# ProgrammateurFilPilote_1_3.net
KiCad netlist of a schematic drawn in EAGLE
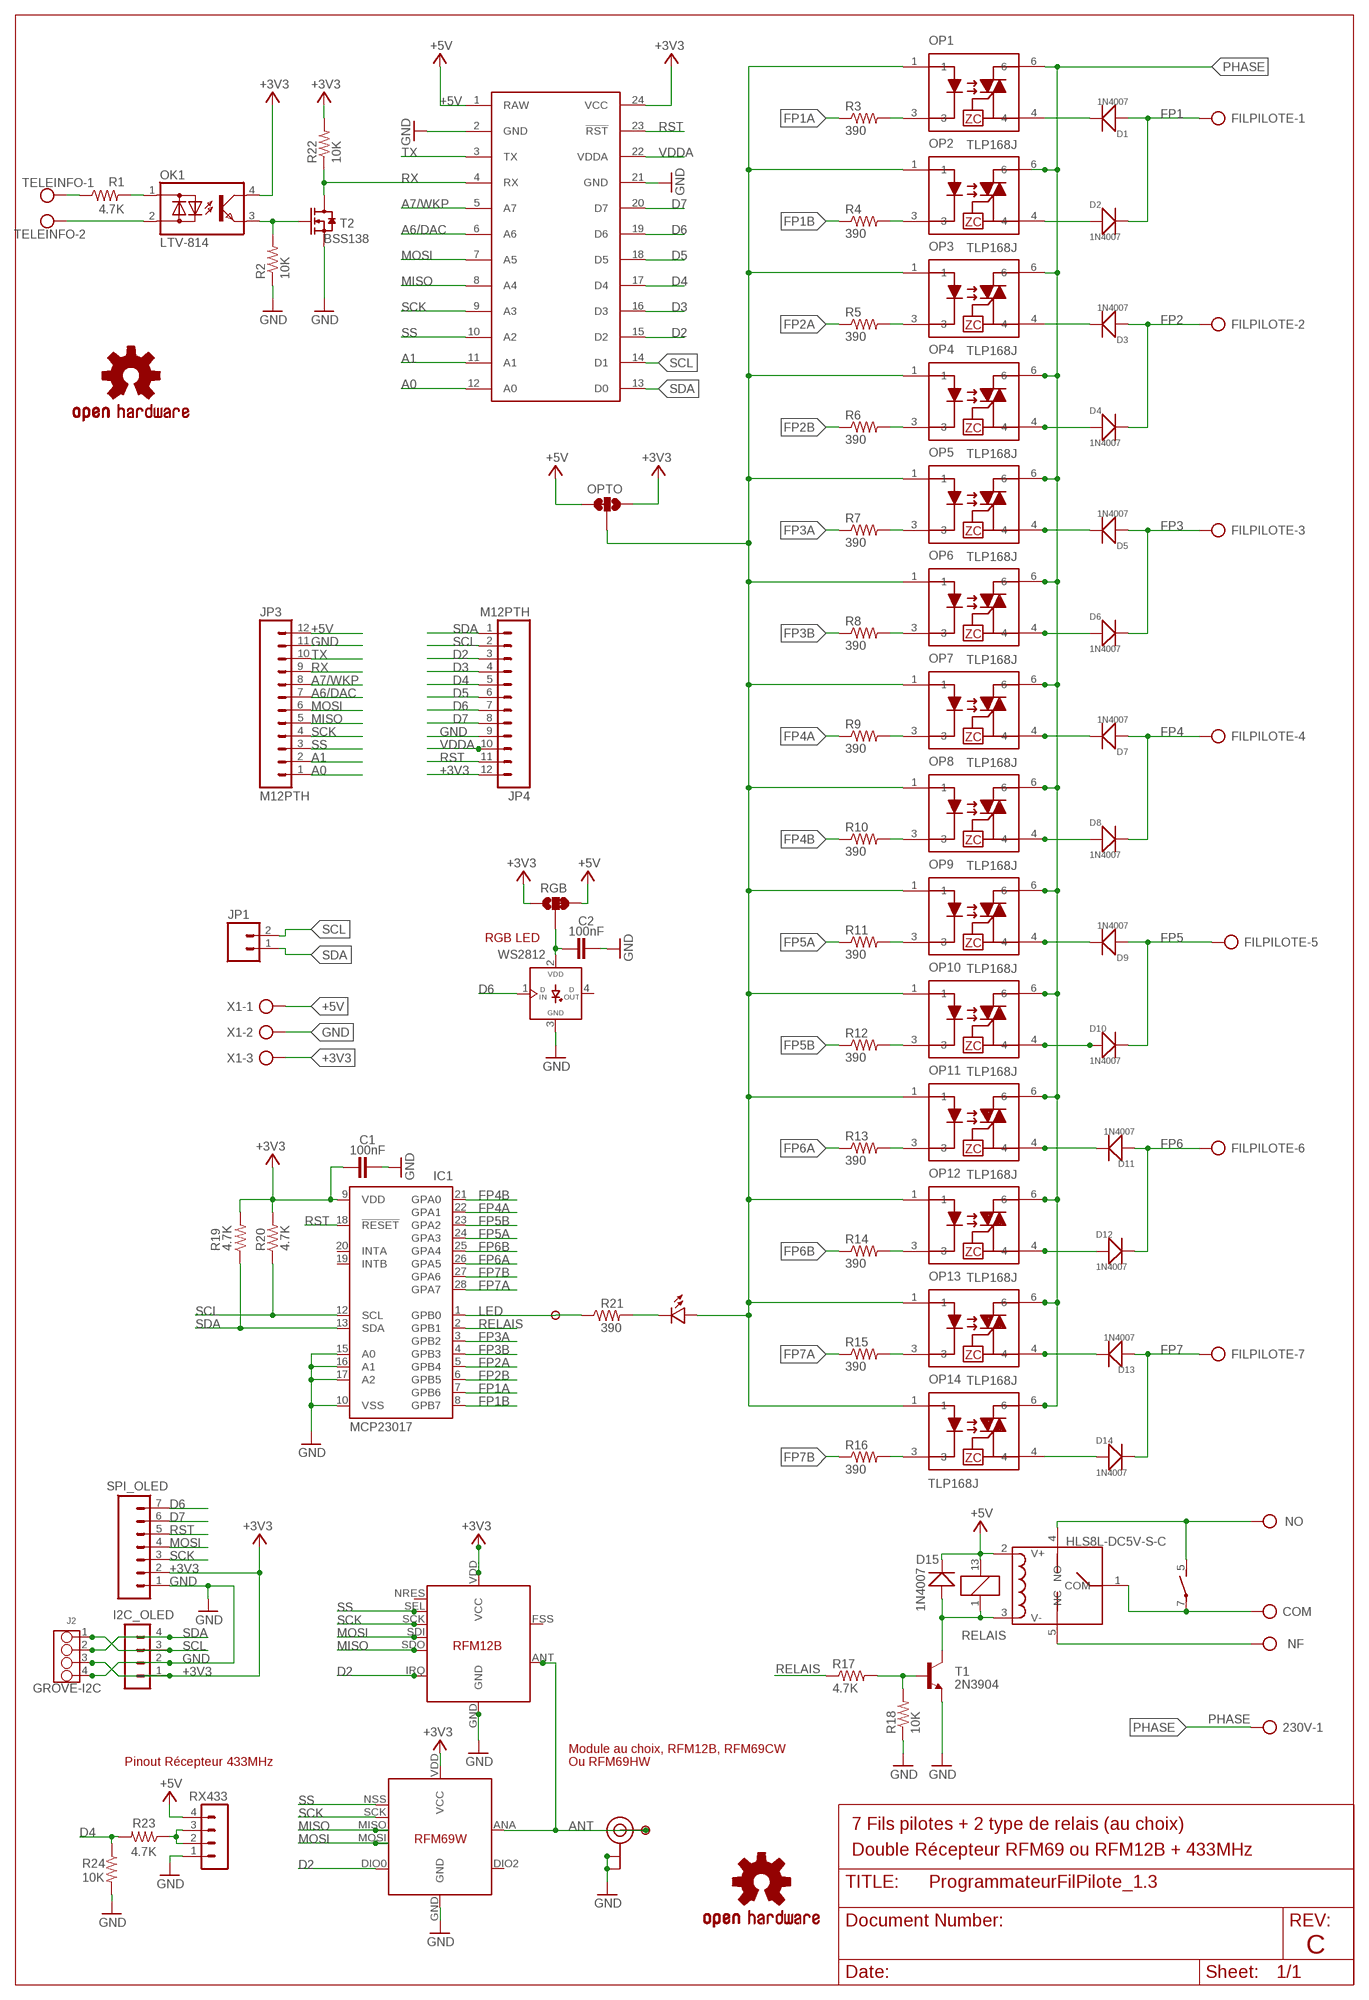
[diagram p0: schematic, sheet 1]

(export (version "E")
  (design (tool "Eeschema 10.0.6"))
  (components
    (comp (ref "230V")
      (value "AK500/2")
      (footprint "eagle-import:AK500_2")
      (libsource (lib "eagle-import") (part "AK500/2"))
    )
    (comp (ref "C1")
      (value "100nF")
      (footprint "eagle-import:1206-CAP")
      (libsource (lib "eagle-import") (part "CAP'1206-CAP'"))
    )
    (comp (ref "C2")
      (value "100nF")
      (footprint "eagle-import:1206-CAP")
      (libsource (lib "eagle-import") (part "CAP'1206-CAP'"))
    )
    (comp (ref "D1")
      (value "1N4007")
      (footprint "eagle-import:DO-214AC")
      (libsource (lib "eagle-import") (part "DIODE'SMA'"))
    )
    (comp (ref "D2")
      (value "1N4007")
      (footprint "eagle-import:DO-214AC")
      (libsource (lib "eagle-import") (part "DIODE'SMA'"))
    )
    (comp (ref "D3")
      (value "1N4007")
      (footprint "eagle-import:DO-214AC")
      (libsource (lib "eagle-import") (part "DIODE'SMA'"))
    )
    (comp (ref "D4")
      (value "1N4007")
      (footprint "eagle-import:DO-214AC")
      (libsource (lib "eagle-import") (part "DIODE'SMA'"))
    )
    (comp (ref "D5")
      (value "1N4007")
      (footprint "eagle-import:DO-214AC")
      (libsource (lib "eagle-import") (part "DIODE'SMA'"))
    )
    (comp (ref "D6")
      (value "1N4007")
      (footprint "eagle-import:DO-214AC")
      (libsource (lib "eagle-import") (part "DIODE'SMA'"))
    )
    (comp (ref "D7")
      (value "1N4007")
      (footprint "eagle-import:DO-214AC")
      (libsource (lib "eagle-import") (part "DIODE'SMA'"))
    )
    (comp (ref "D8")
      (value "1N4007")
      (footprint "eagle-import:DO-214AC")
      (libsource (lib "eagle-import") (part "DIODE'SMA'"))
    )
    (comp (ref "D9")
      (value "1N4007")
      (footprint "eagle-import:DO-214AC")
      (libsource (lib "eagle-import") (part "DIODE'SMA'"))
    )
    (comp (ref "D10")
      (value "1N4007")
      (footprint "eagle-import:DO-214AC")
      (libsource (lib "eagle-import") (part "DIODE'SMA'"))
    )
    (comp (ref "D11")
      (value "1N4007")
      (footprint "eagle-import:DO-214AC")
      (libsource (lib "eagle-import") (part "DIODE'SMA'"))
    )
    (comp (ref "D12")
      (value "1N4007")
      (footprint "eagle-import:DO-214AC")
      (libsource (lib "eagle-import") (part "DIODE'SMA'"))
    )
    (comp (ref "D13")
      (value "1N4007")
      (footprint "eagle-import:DO-214AC")
      (libsource (lib "eagle-import") (part "DIODE'SMA'"))
    )
    (comp (ref "D14")
      (value "1N4007")
      (footprint "eagle-import:DO-214AC")
      (libsource (lib "eagle-import") (part "DIODE'SMA'"))
    )
    (comp (ref "D15")
      (value "1N4007")
      (footprint "eagle-import:DO-214AC")
      (libsource (lib "eagle-import") (part "DIODE'SMA'"))
    )
    (comp (ref "FILPILOTE")
      (value "AK500/7")
      (footprint "eagle-import:AK500_7")
      (libsource (lib "eagle-import") (part "AK500/7"))
    )
    (comp (ref "I2C_OLED")
      (value "CON_HEADER_1X04'SMALL''")
      (footprint "eagle-import:M1X4")
      (libsource (lib "eagle-import") (part "CON_HEADER_1X04'SMALL''"))
    )
    (comp (ref "IC1")
      (value "MCP23017")
      (footprint "eagle-import:DIL28-3")
      (libsource (lib "eagle-import") (part "MCP23017SP"))
    )
    (comp (ref "J2")
      (value "GROVE-I2C")
      (footprint "eagle-import:4P-2.0")
      (libsource (lib "eagle-import") (part "GROVE-4P-2.0-3470130P1"))
    )
    (comp (ref "JP1")
      (value "M02PTH")
      (footprint "eagle-import:1X02")
      (libsource (lib "eagle-import") (part "M02PTH"))
    )
    (comp (ref "JP3")
      (value "M12PTH")
      (footprint "eagle-import:1X12-SMALL-PADS")
      (libsource (lib "eagle-import") (part "M12PTH"))
    )
    (comp (ref "JP4")
      (value "M12PTH")
      (footprint "eagle-import:1X12-SMALL-PADS")
      (libsource (lib "eagle-import") (part "M12PTH"))
    )
    (comp (ref "LED")
      (value "LED3MM")
      (footprint "eagle-import:LED3MM")
      (libsource (lib "eagle-import") (part "LED3MM"))
    )
    (comp (ref "LOGO1")
      (value "OSHW-LOGOL")
      (footprint "eagle-import:OSHW-LOGO-L")
      (libsource (lib "eagle-import") (part "OSHW-LOGOL"))
    )
    (comp (ref "LOGO2")
      (value "OSHW-LOGOL")
      (footprint "eagle-import:OSHW-LOGO-L")
      (libsource (lib "eagle-import") (part "OSHW-LOGOL"))
    )
    (comp (ref "OK1")
      (value "LTV-814")
      (footprint "eagle-import:DIL4-SMD")
      (fields (field (name "MF") "VISHAY/TELEFUNKEN") (field (name "MPN") "SFH6206-3"))
      (libsource (lib "eagle-import") (part "SFH6206"))
    )
    (comp (ref "OP1")
      (value "TLP168J")
      (footprint "eagle-import:MFSOP-4-HANDSOLDER")
      (libsource (lib "eagle-import") (part "TLP168JBIGPAD"))
    )
    (comp (ref "OP2")
      (value "TLP168J")
      (footprint "eagle-import:MFSOP-4-HANDSOLDER")
      (libsource (lib "eagle-import") (part "TLP168JBIGPAD"))
    )
    (comp (ref "OP3")
      (value "TLP168J")
      (footprint "eagle-import:MFSOP-4-HANDSOLDER")
      (libsource (lib "eagle-import") (part "TLP168JBIGPAD"))
    )
    (comp (ref "OP4")
      (value "TLP168J")
      (footprint "eagle-import:MFSOP-4-HANDSOLDER")
      (libsource (lib "eagle-import") (part "TLP168JBIGPAD"))
    )
    (comp (ref "OP5")
      (value "TLP168J")
      (footprint "eagle-import:MFSOP-4-HANDSOLDER")
      (libsource (lib "eagle-import") (part "TLP168JBIGPAD"))
    )
    (comp (ref "OP6")
      (value "TLP168J")
      (footprint "eagle-import:MFSOP-4-HANDSOLDER")
      (libsource (lib "eagle-import") (part "TLP168JBIGPAD"))
    )
    (comp (ref "OP7")
      (value "TLP168J")
      (footprint "eagle-import:MFSOP-4-HANDSOLDER")
      (libsource (lib "eagle-import") (part "TLP168JBIGPAD"))
    )
    (comp (ref "OP8")
      (value "TLP168J")
      (footprint "eagle-import:MFSOP-4-HANDSOLDER")
      (libsource (lib "eagle-import") (part "TLP168JBIGPAD"))
    )
    (comp (ref "OP9")
      (value "TLP168J")
      (footprint "eagle-import:MFSOP-4-HANDSOLDER")
      (libsource (lib "eagle-import") (part "TLP168JBIGPAD"))
    )
    (comp (ref "OP10")
      (value "TLP168J")
      (footprint "eagle-import:MFSOP-4-HANDSOLDER")
      (libsource (lib "eagle-import") (part "TLP168JBIGPAD"))
    )
    (comp (ref "OP11")
      (value "TLP168J")
      (footprint "eagle-import:MFSOP-4-HANDSOLDER")
      (libsource (lib "eagle-import") (part "TLP168JBIGPAD"))
    )
    (comp (ref "OP12")
      (value "TLP168J")
      (footprint "eagle-import:MFSOP-4-HANDSOLDER")
      (libsource (lib "eagle-import") (part "TLP168JBIGPAD"))
    )
    (comp (ref "OP13")
      (value "TLP168J")
      (footprint "eagle-import:MFSOP-4-HANDSOLDER")
      (libsource (lib "eagle-import") (part "TLP168JBIGPAD"))
    )
    (comp (ref "OP14")
      (value "TLP168J")
      (footprint "eagle-import:MFSOP-4-HANDSOLDER")
      (libsource (lib "eagle-import") (part "TLP168JBIGPAD"))
    )
    (comp (ref "OPTO")
      (value "JUMPER-PAD-3-2OF3_NC_BY_TRACE_LARGE")
      (footprint "eagle-import:PAD-JUMPER-3-2OF3_NC_BY_TRACE_YES_SILK_LARGE")
      (libsource (lib "eagle-import") (part "JUMPER-PAD-3-2OF3_NC_BY_TRACE_LARGE"))
    )
    (comp (ref "P1")
      (value "PADSMALL")
      (footprint "eagle-import:PAD-SMALL")
      (libsource (lib "eagle-import") (part "PADSMALL"))
    )
    (comp (ref "P2")
      (value "PADSMALL")
      (footprint "eagle-import:PAD-SMALL")
      (libsource (lib "eagle-import") (part "PADSMALL"))
    )
    (comp (ref "PARTICLE")
      (value "Spark/Photon")
      (footprint "eagle-import:SPARK_CORE")
      (libsource (lib "eagle-import") (part "SPARK_CORECORE"))
    )
    (comp (ref "R1")
      (value "4.7K")
      (footprint "eagle-import:1206-RES")
      (libsource (lib "eagle-import") (part "RESISTOR'1206-RES''"))
    )
    (comp (ref "R2")
      (value "10K")
      (footprint "eagle-import:1206-RES")
      (libsource (lib "eagle-import") (part "RESISTOR'1206-RES''"))
    )
    (comp (ref "R3")
      (value "390")
      (footprint "eagle-import:1206-RES")
      (libsource (lib "eagle-import") (part "RESISTOR'1206-RES''"))
    )
    (comp (ref "R4")
      (value "390")
      (footprint "eagle-import:1206-RES")
      (libsource (lib "eagle-import") (part "RESISTOR'1206-RES''"))
    )
    (comp (ref "R5")
      (value "390")
      (footprint "eagle-import:1206-RES")
      (libsource (lib "eagle-import") (part "RESISTOR'1206-RES''"))
    )
    (comp (ref "R6")
      (value "390")
      (footprint "eagle-import:1206-RES")
      (libsource (lib "eagle-import") (part "RESISTOR'1206-RES''"))
    )
    (comp (ref "R7")
      (value "390")
      (footprint "eagle-import:1206-RES")
      (libsource (lib "eagle-import") (part "RESISTOR'1206-RES''"))
    )
    (comp (ref "R8")
      (value "390")
      (footprint "eagle-import:1206-RES")
      (libsource (lib "eagle-import") (part "RESISTOR'1206-RES''"))
    )
    (comp (ref "R9")
      (value "390")
      (footprint "eagle-import:1206-RES")
      (libsource (lib "eagle-import") (part "RESISTOR'1206-RES''"))
    )
    (comp (ref "R10")
      (value "390")
      (footprint "eagle-import:1206-RES")
      (libsource (lib "eagle-import") (part "RESISTOR'1206-RES''"))
    )
    (comp (ref "R11")
      (value "390")
      (footprint "eagle-import:1206-RES")
      (libsource (lib "eagle-import") (part "RESISTOR'1206-RES''"))
    )
    (comp (ref "R12")
      (value "390")
      (footprint "eagle-import:1206-RES")
      (libsource (lib "eagle-import") (part "RESISTOR'1206-RES''"))
    )
    (comp (ref "R13")
      (value "390")
      (footprint "eagle-import:1206-RES")
      (libsource (lib "eagle-import") (part "RESISTOR'1206-RES''"))
    )
    (comp (ref "R14")
      (value "390")
      (footprint "eagle-import:1206-RES")
      (libsource (lib "eagle-import") (part "RESISTOR'1206-RES''"))
    )
    (comp (ref "R15")
      (value "390")
      (footprint "eagle-import:1206-RES")
      (libsource (lib "eagle-import") (part "RESISTOR'1206-RES''"))
    )
    (comp (ref "R16")
      (value "390")
      (footprint "eagle-import:1206-RES")
      (libsource (lib "eagle-import") (part "RESISTOR'1206-RES''"))
    )
    (comp (ref "R17")
      (value "4.7K")
      (footprint "eagle-import:1206-RES")
      (libsource (lib "eagle-import") (part "RESISTOR'1206-RES''"))
    )
    (comp (ref "R18")
      (value "10K")
      (footprint "eagle-import:1206-RES")
      (libsource (lib "eagle-import") (part "RESISTOR'1206-RES''"))
    )
    (comp (ref "R19")
      (value "4.7K")
      (footprint "eagle-import:1206-RES")
      (libsource (lib "eagle-import") (part "RESISTOR'1206-RES''"))
    )
    (comp (ref "R20")
      (value "4.7K")
      (footprint "eagle-import:1206-RES")
      (libsource (lib "eagle-import") (part "RESISTOR'1206-RES''"))
    )
    (comp (ref "R21")
      (value "390")
      (footprint "eagle-import:1206-RES")
      (libsource (lib "eagle-import") (part "RESISTOR'1206-RES''"))
    )
    (comp (ref "R22")
      (value "10K")
      (footprint "eagle-import:1206-RES")
      (libsource (lib "eagle-import") (part "RESISTOR'1206-RES''"))
    )
    (comp (ref "R23")
      (value "4.7K")
      (footprint "eagle-import:1206-RES")
      (libsource (lib "eagle-import") (part "RESISTOR'1206-RES''"))
    )
    (comp (ref "R24")
      (value "10K")
      (footprint "eagle-import:1206-RES")
      (libsource (lib "eagle-import") (part "RESISTOR'1206-RES''"))
    )
    (comp (ref "RELAIS")
      (value "Relais G6D")
      (footprint "eagle-import:G6D")
      (libsource (lib "eagle-import") (part "G6D?-1A-ASI12VDC"))
    )
    (comp (ref "RGB")
      (value "JUMPER-PAD-3-2OF3_NC_BY_TRACE_SMALL")
      (footprint "eagle-import:PAD-JUMPER-3-2OF3_NC_BY_TRACE_YES_SILK_FULL_BOX")
      (libsource (lib "eagle-import") (part "JUMPER-PAD-3-2OF3_NC_BY_TRACE_SMALL"))
    )
    (comp (ref "RL")
      (value "AK500/2")
      (footprint "eagle-import:AK500_2")
      (libsource (lib "eagle-import") (part "AK500/2"))
    )
    (comp (ref "RX433")
      (value "CON_HEADER_1X04'NO_LOCK'")
      (footprint "eagle-import:1X04_NO_LOCK")
      (libsource (lib "eagle-import") (part "CON_HEADER_1X04'NO_LOCK'"))
    )
    (comp (ref "SPI_OLED")
      (value "CON_HEADER_1X07'SMALL'")
      (footprint "eagle-import:M1X7")
      (libsource (lib "eagle-import") (part "CON_HEADER_1X07'SMALL'"))
    )
    (comp (ref "SW1")
      (value "HLS8L-DC5V-S-C")
      (footprint "eagle-import:5P-L19.0XW15.0XH15.0MM")
      (libsource (lib "eagle-import") (part "RELAY-HLS8L-DC5V-S-C-315030000"))
    )
    (comp (ref "T1")
      (value "2N3904")
      (footprint "eagle-import:TO92-EBC")
      (libsource (lib "eagle-import") (part "-NPN-TO92-EBC2N2222"))
    )
    (comp (ref "T2")
      (value "BSS138")
      (footprint "eagle-import:SOT23")
      (libsource (lib "eagle-import") (part "MOSFET-N-''"))
    )
    (comp (ref "TELEINFO")
      (value "AK500/2")
      (footprint "eagle-import:AK500_2")
      (libsource (lib "eagle-import") (part "AK500/2"))
    )
    (comp (ref "U$2")
      (value "RFM12B")
      (footprint "eagle-import:RFM12B-MINPADS")
      (libsource (lib "eagle-import") (part "RFM12B"))
    )
    (comp (ref "U$3")
      (value "RFM69W")
      (footprint "eagle-import:RFM69W-MINPADS")
      (libsource (lib "eagle-import") (part "RFM69W"))
    )
    (comp (ref "U-FL")
      (value "U.FL")
      (footprint "eagle-import:U.FL")
      (libsource (lib "eagle-import") (part "U.FL"))
    )
    (comp (ref "WS2812")
      (value "RGB LED")
      (footprint "eagle-import:WS2812-PTH")
      (libsource (lib "eagle-import") (part "WS2812B5MM"))
    )
    (comp (ref "X1")
      (value "AK500/3")
      (footprint "eagle-import:AK500_3")
      (libsource (lib "eagle-import") (part "AK500/3"))
    )
  )
  (nets
    (net (code "1") (name "+3V3") (class "Default")
      (node (ref "C1") (pin "1") (pinfunction "1_1") (pintype "passive"))
      (node (ref "I2C_OLED") (pin "1") (pinfunction "1_1") (pintype "passive"))
      (node (ref "IC1") (pin "9") (pinfunction "VDD_9") (pintype "power_in"))
      (node (ref "J2") (pin "3") (pinfunction "3_3") (pintype "bidirectional"))
      (node (ref "JP4") (pin "12") (pinfunction "12_12") (pintype "passive"))
      (node (ref "OK1") (pin "4") (pinfunction "C_4") (pintype "passive"))
      (node (ref "OPTO") (pin "1") (pinfunction "1_1") (pintype "passive"))
      (node (ref "PARTICLE") (pin "24") (pinfunction "VCC_24") (pintype "power_in"))
      (node (ref "R19") (pin "2") (pinfunction "2_2") (pintype "passive"))
      (node (ref "R20") (pin "2") (pinfunction "2_2") (pintype "passive"))
      (node (ref "R22") (pin "2") (pinfunction "2_2") (pintype "passive"))
      (node (ref "RGB") (pin "1") (pinfunction "1_1") (pintype "passive"))
      (node (ref "SPI_OLED") (pin "2") (pinfunction "2_2") (pintype "passive"))
      (node (ref "U$2") (pin "VDD") (pinfunction "VCC_VDD") (pintype "power_in"))
      (node (ref "U$3") (pin "VDD") (pinfunction "VCC_VDD") (pintype "power_in"))
      (node (ref "X1") (pin "3") (pinfunction "KL_3") (pintype "passive"))
    )
    (net (code "2") (name "+5V") (class "Default")
      (node (ref "D15") (pin "2") (pinfunction "-_2") (pintype "passive"))
      (node (ref "JP3") (pin "12") (pinfunction "12_12") (pintype "passive"))
      (node (ref "OPTO") (pin "3") (pinfunction "3_3") (pintype "passive"))
      (node (ref "PARTICLE") (pin "1") (pinfunction "RAW_1") (pintype "power_in"))
      (node (ref "RELAIS") (pin "13") (pinfunction "2_13") (pintype "passive"))
      (node (ref "RGB") (pin "3") (pinfunction "3_3") (pintype "passive"))
      (node (ref "RX433") (pin "4") (pinfunction "4_4") (pintype "passive"))
      (node (ref "SW1") (pin "2") (pinfunction "V+_2") (pintype "bidirectional"))
      (node (ref "X1") (pin "1") (pinfunction "KL_1") (pintype "passive"))
    )
    (net (code "3") (name "/A0") (class "Default")
      (node (ref "JP3") (pin "1") (pinfunction "1_1") (pintype "passive"))
      (node (ref "PARTICLE") (pin "12") (pinfunction "A0_12") (pintype "bidirectional"))
    )
    (net (code "4") (name "/A1") (class "Default")
      (node (ref "JP3") (pin "2") (pinfunction "2_2") (pintype "passive"))
      (node (ref "PARTICLE") (pin "11") (pinfunction "A1_11") (pintype "bidirectional"))
    )
    (net (code "5") (name "/A6{slash}DAC") (class "Default")
      (node (ref "JP3") (pin "7") (pinfunction "7_7") (pintype "passive"))
      (node (ref "PARTICLE") (pin "6") (pinfunction "A6_6") (pintype "bidirectional"))
    )
    (net (code "6") (name "/A7{slash}WKP") (class "Default")
      (node (ref "JP3") (pin "8") (pinfunction "8_8") (pintype "passive"))
      (node (ref "PARTICLE") (pin "5") (pinfunction "A7_5") (pintype "bidirectional"))
    )
    (net (code "7") (name "/ANT") (class "Default")
      (node (ref "P1") (pin "1") (pinfunction "1_1") (pintype "bidirectional"))
      (node (ref "U$2") (pin "ANT") (pinfunction "ANT_ANT") (pintype "passive"))
      (node (ref "U$3") (pin "ANA") (pinfunction "ANT_ANA") (pintype "passive"))
      (node (ref "U-FL") (pin "3") (pinfunction "SIGNAL_3") (pintype "passive"))
    )
    (net (code "8") (name "/COM") (class "Default")
      (node (ref "RELAIS") (pin "7") (pinfunction "P_7") (pintype "passive"))
      (node (ref "RL") (pin "1") (pinfunction "KL_1") (pintype "passive"))
      (node (ref "SW1") (pin "1") (pinfunction "COM_1") (pintype "bidirectional"))
    )
    (net (code "9") (name "/D2") (class "Default")
      (node (ref "JP4") (pin "3") (pinfunction "3_3") (pintype "passive"))
      (node (ref "PARTICLE") (pin "15") (pinfunction "D2_15") (pintype "bidirectional"))
      (node (ref "U$2") (pin "IRQ") (pinfunction "IRQ_IRQ") (pintype "open_collector"))
      (node (ref "U$3") (pin "DIO0") (pinfunction "DIO0_DIO0") (pintype "open_collector"))
    )
    (net (code "10") (name "/D3") (class "Default")
      (node (ref "JP4") (pin "4") (pinfunction "4_4") (pintype "passive"))
      (node (ref "PARTICLE") (pin "16") (pinfunction "D3_16") (pintype "bidirectional"))
    )
    (net (code "11") (name "/D4") (class "Default")
      (node (ref "JP4") (pin "5") (pinfunction "5_5") (pintype "passive"))
      (node (ref "PARTICLE") (pin "17") (pinfunction "D4_17") (pintype "bidirectional"))
      (node (ref "R23") (pin "2") (pinfunction "2_2") (pintype "passive"))
      (node (ref "R24") (pin "1") (pinfunction "1_1") (pintype "passive"))
    )
    (net (code "12") (name "/D5") (class "Default")
      (node (ref "JP4") (pin "6") (pinfunction "6_6") (pintype "passive"))
      (node (ref "PARTICLE") (pin "18") (pinfunction "D5_18") (pintype "bidirectional"))
    )
    (net (code "13") (name "/D6") (class "Default")
      (node (ref "JP4") (pin "7") (pinfunction "7_7") (pintype "passive"))
      (node (ref "PARTICLE") (pin "19") (pinfunction "D6_19") (pintype "bidirectional"))
      (node (ref "SPI_OLED") (pin "7") (pinfunction "7_7") (pintype "passive"))
      (node (ref "WS2812") (pin "1") (pinfunction "DIN_1") (pintype "input"))
    )
    (net (code "14") (name "/D7") (class "Default")
      (node (ref "JP4") (pin "8") (pinfunction "8_8") (pintype "passive"))
      (node (ref "PARTICLE") (pin "20") (pinfunction "D7_20") (pintype "bidirectional"))
      (node (ref "SPI_OLED") (pin "6") (pinfunction "6_6") (pintype "passive"))
    )
    (net (code "15") (name "/FP1") (class "Default")
      (node (ref "D1") (pin "1") (pinfunction "+_1") (pintype "passive"))
      (node (ref "D2") (pin "2") (pinfunction "-_2") (pintype "passive"))
      (node (ref "FILPILOTE") (pin "1") (pinfunction "KL_1") (pintype "passive"))
    )
    (net (code "16") (name "/FP2") (class "Default")
      (node (ref "D3") (pin "1") (pinfunction "+_1") (pintype "passive"))
      (node (ref "D4") (pin "2") (pinfunction "-_2") (pintype "passive"))
      (node (ref "FILPILOTE") (pin "2") (pinfunction "KL_2") (pintype "passive"))
    )
    (net (code "17") (name "/FP3") (class "Default")
      (node (ref "D5") (pin "1") (pinfunction "+_1") (pintype "passive"))
      (node (ref "D6") (pin "2") (pinfunction "-_2") (pintype "passive"))
      (node (ref "FILPILOTE") (pin "3") (pinfunction "KL_3") (pintype "passive"))
    )
    (net (code "18") (name "/FP4") (class "Default")
      (node (ref "D7") (pin "1") (pinfunction "+_1") (pintype "passive"))
      (node (ref "D8") (pin "2") (pinfunction "-_2") (pintype "passive"))
      (node (ref "FILPILOTE") (pin "4") (pinfunction "KL_4") (pintype "passive"))
    )
    (net (code "19") (name "/FP5") (class "Default")
      (node (ref "D10") (pin "2") (pinfunction "-_2") (pintype "passive"))
      (node (ref "D9") (pin "1") (pinfunction "+_1") (pintype "passive"))
      (node (ref "FILPILOTE") (pin "5") (pinfunction "KL_5") (pintype "passive"))
    )
    (net (code "20") (name "/FP6") (class "Default")
      (node (ref "D11") (pin "1") (pinfunction "+_1") (pintype "passive"))
      (node (ref "D12") (pin "2") (pinfunction "-_2") (pintype "passive"))
      (node (ref "FILPILOTE") (pin "6") (pinfunction "KL_6") (pintype "passive"))
    )
    (net (code "21") (name "/FP7") (class "Default")
      (node (ref "D13") (pin "1") (pinfunction "+_1") (pintype "passive"))
      (node (ref "D14") (pin "2") (pinfunction "-_2") (pintype "passive"))
      (node (ref "FILPILOTE") (pin "7") (pinfunction "KL_7") (pintype "passive"))
    )
    (net (code "22") (name "/LED") (class "Default")
      (node (ref "IC1") (pin "1") (pinfunction "GPB0_1") (pintype "bidirectional"))
      (node (ref "P2") (pin "1") (pinfunction "1_1") (pintype "bidirectional"))
      (node (ref "R21") (pin "1") (pinfunction "1_1") (pintype "passive"))
    )
    (net (code "23") (name "/MISO") (class "Default")
      (node (ref "JP3") (pin "5") (pinfunction "5_5") (pintype "passive"))
      (node (ref "PARTICLE") (pin "8") (pinfunction "A4_8") (pintype "bidirectional"))
      (node (ref "U$2") (pin "SDO") (pinfunction "SDO_SDO") (pintype "output"))
      (node (ref "U$3") (pin "MISO") (pinfunction "MISO_MISO") (pintype "input"))
    )
    (net (code "24") (name "/MOSI") (class "Default")
      (node (ref "JP3") (pin "6") (pinfunction "6_6") (pintype "passive"))
      (node (ref "PARTICLE") (pin "7") (pinfunction "A5_7") (pintype "bidirectional"))
      (node (ref "SPI_OLED") (pin "4") (pinfunction "4_4") (pintype "passive"))
      (node (ref "U$2") (pin "SDI") (pinfunction "SDI_SDI") (pintype "input"))
      (node (ref "U$3") (pin "MOSI") (pinfunction "MOSI_MOSI") (pintype "output"))
    )
    (net (code "25") (name "/NF") (class "Default")
      (node (ref "RL") (pin "2") (pinfunction "KL_2") (pintype "passive"))
      (node (ref "SW1") (pin "5") (pinfunction "NC_5") (pintype "bidirectional"))
    )
    (net (code "26") (name "/NO") (class "Default")
      (node (ref "230V") (pin "2") (pinfunction "KL_2") (pintype "passive"))
      (node (ref "RELAIS") (pin "5") (pinfunction "S_5") (pintype "passive"))
      (node (ref "SW1") (pin "4") (pinfunction "NO_4") (pintype "bidirectional"))
    )
    (net (code "27") (name "/RELAIS") (class "Default")
      (node (ref "IC1") (pin "2") (pinfunction "GPB1_2") (pintype "bidirectional"))
      (node (ref "R17") (pin "1") (pinfunction "1_1") (pintype "passive"))
    )
    (net (code "28") (name "/RST") (class "Default")
      (node (ref "IC1") (pin "18") (pinfunction "~{RESET}_18") (pintype "input"))
      (node (ref "JP4") (pin "11") (pinfunction "11_11") (pintype "passive"))
      (node (ref "PARTICLE") (pin "23") (pinfunction "~{RST}_23") (pintype "bidirectional"))
      (node (ref "SPI_OLED") (pin "5") (pinfunction "5_5") (pintype "passive"))
    )
    (net (code "29") (name "/RX") (class "Default")
      (node (ref "JP3") (pin "9") (pinfunction "9_9") (pintype "passive"))
      (node (ref "PARTICLE") (pin "4") (pinfunction "RX_4") (pintype "bidirectional"))
      (node (ref "R22") (pin "1") (pinfunction "1_1") (pintype "passive"))
      (node (ref "T2") (pin "3") (pinfunction "D_3") (pintype "passive"))
    )
    (net (code "30") (name "/SCK") (class "Default")
      (node (ref "JP3") (pin "4") (pinfunction "4_4") (pintype "passive"))
      (node (ref "PARTICLE") (pin "9") (pinfunction "A3_9") (pintype "bidirectional"))
      (node (ref "SPI_OLED") (pin "3") (pinfunction "3_3") (pintype "passive"))
      (node (ref "U$2") (pin "SCK") (pinfunction "SCK_SCK") (pintype "input"))
      (node (ref "U$3") (pin "SCK") (pinfunction "SCK_SCK") (pintype "input"))
    )
    (net (code "31") (name "/SS") (class "Default")
      (node (ref "JP3") (pin "3") (pinfunction "3_3") (pintype "passive"))
      (node (ref "PARTICLE") (pin "10") (pinfunction "A2_10") (pintype "bidirectional"))
      (node (ref "U$2") (pin "SEL") (pinfunction "SEL_SEL") (pintype "input"))
      (node (ref "U$3") (pin "NSS") (pinfunction "SEL_NSS") (pintype "input"))
    )
    (net (code "32") (name "/TX") (class "Default")
      (node (ref "JP3") (pin "10") (pinfunction "10_10") (pintype "passive"))
      (node (ref "PARTICLE") (pin "3") (pinfunction "TX_3") (pintype "bidirectional"))
    )
    (net (code "33") (name "/VDDA") (class "Default")
      (node (ref "JP4") (pin "10") (pinfunction "10_10") (pintype "passive"))
      (node (ref "PARTICLE") (pin "22") (pinfunction "VDDA_22") (pintype "power_in"))
    )
    (net (code "34") (name "FP1A") (class "Default")
      (node (ref "IC1") (pin "7") (pinfunction "GPB6_7") (pintype "bidirectional"))
      (node (ref "R3") (pin "1") (pinfunction "1_1") (pintype "passive"))
    )
    (net (code "35") (name "FP1B") (class "Default")
      (node (ref "IC1") (pin "8") (pinfunction "GPB7_8") (pintype "bidirectional"))
      (node (ref "R4") (pin "1") (pinfunction "1_1") (pintype "passive"))
    )
    (net (code "36") (name "FP2A") (class "Default")
      (node (ref "IC1") (pin "5") (pinfunction "GPB4_5") (pintype "bidirectional"))
      (node (ref "R5") (pin "1") (pinfunction "1_1") (pintype "passive"))
    )
    (net (code "37") (name "FP2B") (class "Default")
      (node (ref "IC1") (pin "6") (pinfunction "GPB5_6") (pintype "bidirectional"))
      (node (ref "R6") (pin "1") (pinfunction "1_1") (pintype "passive"))
    )
    (net (code "38") (name "FP3A") (class "Default")
      (node (ref "IC1") (pin "3") (pinfunction "GPB2_3") (pintype "bidirectional"))
      (node (ref "R7") (pin "1") (pinfunction "1_1") (pintype "passive"))
    )
    (net (code "39") (name "FP3B") (class "Default")
      (node (ref "IC1") (pin "4") (pinfunction "GPB3_4") (pintype "bidirectional"))
      (node (ref "R8") (pin "1") (pinfunction "1_1") (pintype "passive"))
    )
    (net (code "40") (name "FP4A") (class "Default")
      (node (ref "IC1") (pin "22") (pinfunction "GPA1_22") (pintype "bidirectional"))
      (node (ref "R9") (pin "1") (pinfunction "1_1") (pintype "passive"))
    )
    (net (code "41") (name "FP4B") (class "Default")
      (node (ref "IC1") (pin "21") (pinfunction "GPA0_21") (pintype "bidirectional"))
      (node (ref "R10") (pin "1") (pinfunction "1_1") (pintype "passive"))
    )
    (net (code "42") (name "FP5A") (class "Default")
      (node (ref "IC1") (pin "24") (pinfunction "GPA3_24") (pintype "bidirectional"))
      (node (ref "R11") (pin "1") (pinfunction "1_1") (pintype "passive"))
    )
    (net (code "43") (name "FP5B") (class "Default")
      (node (ref "IC1") (pin "23") (pinfunction "GPA2_23") (pintype "bidirectional"))
      (node (ref "R12") (pin "1") (pinfunction "1_1") (pintype "passive"))
    )
    (net (code "44") (name "FP6A") (class "Default")
      (node (ref "IC1") (pin "26") (pinfunction "GPA5_26") (pintype "bidirectional"))
      (node (ref "R13") (pin "1") (pinfunction "1_1") (pintype "passive"))
    )
    (net (code "45") (name "FP6B") (class "Default")
      (node (ref "IC1") (pin "25") (pinfunction "GPA4_25") (pintype "bidirectional"))
      (node (ref "R14") (pin "1") (pinfunction "1_1") (pintype "passive"))
    )
    (net (code "46") (name "FP7A") (class "Default")
      (node (ref "IC1") (pin "28") (pinfunction "GPA7_28") (pintype "bidirectional"))
      (node (ref "R15") (pin "1") (pinfunction "1_1") (pintype "passive"))
    )
    (net (code "47") (name "FP7B") (class "Default")
      (node (ref "IC1") (pin "27") (pinfunction "GPA6_27") (pintype "bidirectional"))
      (node (ref "R16") (pin "1") (pinfunction "1_1") (pintype "passive"))
    )
    (net (code "48") (name "GND") (class "Default")
      (node (ref "C1") (pin "2") (pinfunction "2_2") (pintype "passive"))
      (node (ref "C2") (pin "2") (pinfunction "2_2") (pintype "passive"))
      (node (ref "I2C_OLED") (pin "2") (pinfunction "2_2") (pintype "passive"))
      (node (ref "IC1") (pin "10") (pinfunction "VSS_10") (pintype "power_in"))
      (node (ref "IC1") (pin "15") (pinfunction "A0_15") (pintype "input"))
      (node (ref "IC1") (pin "16") (pinfunction "A1_16") (pintype "input"))
      (node (ref "IC1") (pin "17") (pinfunction "A2_17") (pintype "input"))
      (node (ref "J2") (pin "4") (pinfunction "4_4") (pintype "bidirectional"))
      (node (ref "JP3") (pin "11") (pinfunction "11_11") (pintype "passive"))
      (node (ref "JP4") (pin "9") (pinfunction "9_9") (pintype "passive"))
      (node (ref "PARTICLE") (pin "2") (pinfunction "GND_2") (pintype "power_in"))
      (node (ref "PARTICLE") (pin "21") (pinfunction "GND_21") (pintype "power_in"))
      (node (ref "R18") (pin "1") (pinfunction "1_1") (pintype "passive"))
      (node (ref "R2") (pin "1") (pinfunction "1_1") (pintype "passive"))
      (node (ref "R24") (pin "2") (pinfunction "2_2") (pintype "passive"))
      (node (ref "RX433") (pin "1") (pinfunction "1_1") (pintype "passive"))
      (node (ref "SPI_OLED") (pin "1") (pinfunction "1_1") (pintype "passive"))
      (node (ref "T1") (pin "E") (pinfunction "E_E") (pintype "passive"))
      (node (ref "T2") (pin "2") (pinfunction "S_2") (pintype "passive"))
      (node (ref "U$2") (pin "GND") (pinfunction "GND_GND") (pintype "power_in"))
      (node (ref "U$3") (pin "GND") (pinfunction "GND_GND") (pintype "power_in"))
      (node (ref "U-FL") (pin "1") (pinfunction "GND_1") (pintype "passive"))
      (node (ref "U-FL") (pin "2") (pinfunction "GND_2") (pintype "passive"))
      (node (ref "WS2812") (pin "3") (pinfunction "GND_3") (pintype "power_in"))
      (node (ref "X1") (pin "2") (pinfunction "KL_2") (pintype "passive"))
    )
    (net (code "49") (name "Net-(D1--)") (class "Default")
      (node (ref "D1") (pin "2") (pinfunction "-_2") (pintype "passive"))
      (node (ref "OP1") (pin "4") (pinfunction "4_4") (pintype "bidirectional"))
    )
    (net (code "50") (name "Net-(D2-+)") (class "Default")
      (node (ref "D2") (pin "1") (pinfunction "+_1") (pintype "passive"))
      (node (ref "OP2") (pin "4") (pinfunction "4_4") (pintype "bidirectional"))
    )
    (net (code "51") (name "Net-(D3--)") (class "Default")
      (node (ref "D3") (pin "2") (pinfunction "-_2") (pintype "passive"))
      (node (ref "OP3") (pin "4") (pinfunction "4_4") (pintype "bidirectional"))
    )
    (net (code "52") (name "Net-(D4-+)") (class "Default")
      (node (ref "D4") (pin "1") (pinfunction "+_1") (pintype "passive"))
      (node (ref "OP4") (pin "4") (pinfunction "4_4") (pintype "bidirectional"))
    )
    (net (code "53") (name "Net-(D5--)") (class "Default")
      (node (ref "D5") (pin "2") (pinfunction "-_2") (pintype "passive"))
      (node (ref "OP5") (pin "4") (pinfunction "4_4") (pintype "bidirectional"))
    )
    (net (code "54") (name "Net-(D6-+)") (class "Default")
      (node (ref "D6") (pin "1") (pinfunction "+_1") (pintype "passive"))
      (node (ref "OP6") (pin "4") (pinfunction "4_4") (pintype "bidirectional"))
    )
    (net (code "55") (name "Net-(D7--)") (class "Default")
      (node (ref "D7") (pin "2") (pinfunction "-_2") (pintype "passive"))
      (node (ref "OP7") (pin "4") (pinfunction "4_4") (pintype "bidirectional"))
    )
    (net (code "56") (name "Net-(D8-+)") (class "Default")
      (node (ref "D8") (pin "1") (pinfunction "+_1") (pintype "passive"))
      (node (ref "OP8") (pin "4") (pinfunction "4_4") (pintype "bidirectional"))
    )
    (net (code "57") (name "Net-(D9--)") (class "Default")
      (node (ref "D9") (pin "2") (pinfunction "-_2") (pintype "passive"))
      (node (ref "OP9") (pin "4") (pinfunction "4_4") (pintype "bidirectional"))
    )
    (net (code "58") (name "Net-(D10-+)") (class "Default")
      (node (ref "D10") (pin "1") (pinfunction "+_1") (pintype "passive"))
      (node (ref "OP10") (pin "4") (pinfunction "4_4") (pintype "bidirectional"))
    )
    (net (code "59") (name "Net-(D11--)") (class "Default")
      (node (ref "D11") (pin "2") (pinfunction "-_2") (pintype "passive"))
      (node (ref "OP11") (pin "4") (pinfunction "4_4") (pintype "bidirectional"))
    )
    (net (code "60") (name "Net-(D12-+)") (class "Default")
      (node (ref "D12") (pin "1") (pinfunction "+_1") (pintype "passive"))
      (node (ref "OP12") (pin "4") (pinfunction "4_4") (pintype "bidirectional"))
    )
    (net (code "61") (name "Net-(D13--)") (class "Default")
      (node (ref "D13") (pin "2") (pinfunction "-_2") (pintype "passive"))
      (node (ref "OP13") (pin "4") (pinfunction "4_4") (pintype "bidirectional"))
    )
    (net (code "62") (name "Net-(D14-+)") (class "Default")
      (node (ref "D14") (pin "1") (pinfunction "+_1") (pintype "passive"))
      (node (ref "OP14") (pin "4") (pinfunction "4_4") (pintype "bidirectional"))
    )
    (net (code "63") (name "Net-(D15-+)") (class "Default")
      (node (ref "D15") (pin "1") (pinfunction "+_1") (pintype "passive"))
      (node (ref "RELAIS") (pin "1") (pinfunction "1_1") (pintype "passive"))
      (node (ref "SW1") (pin "3") (pinfunction "V-_3") (pintype "bidirectional"))
      (node (ref "T1") (pin "C") (pinfunction "C_C") (pintype "passive"))
    )
    (net (code "64") (name "Net-(LED-PadMINUS)") (class "Default")
      (node (ref "LED") (pin "MINUS") (pinfunction "MINUS_MINUS") (pintype "passive"))
      (node (ref "R21") (pin "2") (pinfunction "2_2") (pintype "passive"))
    )
    (net (code "65") (name "Net-(LED-PadPLUS)") (class "Default")
      (node (ref "LED") (pin "PLUS") (pinfunction "PLUS_PLUS") (pintype "passive"))
      (node (ref "OP1") (pin "1") (pinfunction "1_1") (pintype "bidirectional"))
      (node (ref "OP10") (pin "1") (pinfunction "1_1") (pintype "bidirectional"))
      (node (ref "OP11") (pin "1") (pinfunction "1_1") (pintype "bidirectional"))
      (node (ref "OP12") (pin "1") (pinfunction "1_1") (pintype "bidirectional"))
      (node (ref "OP13") (pin "1") (pinfunction "1_1") (pintype "bidirectional"))
      (node (ref "OP14") (pin "1") (pinfunction "1_1") (pintype "bidirectional"))
      (node (ref "OP2") (pin "1") (pinfunction "1_1") (pintype "bidirectional"))
      (node (ref "OP3") (pin "1") (pinfunction "1_1") (pintype "bidirectional"))
      (node (ref "OP4") (pin "1") (pinfunction "1_1") (pintype "bidirectional"))
      (node (ref "OP5") (pin "1") (pinfunction "1_1") (pintype "bidirectional"))
      (node (ref "OP6") (pin "1") (pinfunction "1_1") (pintype "bidirectional"))
      (node (ref "OP7") (pin "1") (pinfunction "1_1") (pintype "bidirectional"))
      (node (ref "OP8") (pin "1") (pinfunction "1_1") (pintype "bidirectional"))
      (node (ref "OP9") (pin "1") (pinfunction "1_1") (pintype "bidirectional"))
      (node (ref "OPTO") (pin "2") (pinfunction "2_2") (pintype "passive"))
    )
    (net (code "66") (name "Net-(OK1-AC1)") (class "Default")
      (node (ref "OK1") (pin "1") (pinfunction "AC1_1") (pintype "passive"))
      (node (ref "R1") (pin "2") (pinfunction "2_2") (pintype "passive"))
    )
    (net (code "67") (name "Net-(OK1-AC2)") (class "Default")
      (node (ref "OK1") (pin "2") (pinfunction "AC2_2") (pintype "passive"))
      (node (ref "TELEINFO") (pin "2") (pinfunction "KL_2") (pintype "passive"))
    )
    (net (code "68") (name "Net-(OK1-E)") (class "Default")
      (node (ref "OK1") (pin "3") (pinfunction "E_3") (pintype "passive"))
      (node (ref "R2") (pin "2") (pinfunction "2_2") (pintype "passive"))
      (node (ref "T2") (pin "1") (pinfunction "G_1") (pintype "passive"))
    )
    (net (code "69") (name "Net-(OP1-Pad3)") (class "Default")
      (node (ref "OP1") (pin "3") (pinfunction "3_3") (pintype "bidirectional"))
      (node (ref "R3") (pin "2") (pinfunction "2_2") (pintype "passive"))
    )
    (net (code "70") (name "Net-(OP2-Pad3)") (class "Default")
      (node (ref "OP2") (pin "3") (pinfunction "3_3") (pintype "bidirectional"))
      (node (ref "R4") (pin "2") (pinfunction "2_2") (pintype "passive"))
    )
    (net (code "71") (name "Net-(OP3-Pad3)") (class "Default")
      (node (ref "OP3") (pin "3") (pinfunction "3_3") (pintype "bidirectional"))
      (node (ref "R5") (pin "2") (pinfunction "2_2") (pintype "passive"))
    )
    (net (code "72") (name "Net-(OP4-Pad3)") (class "Default")
      (node (ref "OP4") (pin "3") (pinfunction "3_3") (pintype "bidirectional"))
      (node (ref "R6") (pin "2") (pinfunction "2_2") (pintype "passive"))
    )
    (net (code "73") (name "Net-(OP5-Pad3)") (class "Default")
      (node (ref "OP5") (pin "3") (pinfunction "3_3") (pintype "bidirectional"))
      (node (ref "R7") (pin "2") (pinfunction "2_2") (pintype "passive"))
    )
    (net (code "74") (name "Net-(OP6-Pad3)") (class "Default")
      (node (ref "OP6") (pin "3") (pinfunction "3_3") (pintype "bidirectional"))
      (node (ref "R8") (pin "2") (pinfunction "2_2") (pintype "passive"))
    )
    (net (code "75") (name "Net-(OP7-Pad3)") (class "Default")
      (node (ref "OP7") (pin "3") (pinfunction "3_3") (pintype "bidirectional"))
      (node (ref "R9") (pin "2") (pinfunction "2_2") (pintype "passive"))
    )
    (net (code "76") (name "Net-(OP8-Pad3)") (class "Default")
      (node (ref "OP8") (pin "3") (pinfunction "3_3") (pintype "bidirectional"))
      (node (ref "R10") (pin "2") (pinfunction "2_2") (pintype "passive"))
    )
    (net (code "77") (name "Net-(OP9-Pad3)") (class "Default")
      (node (ref "OP9") (pin "3") (pinfunction "3_3") (pintype "bidirectional"))
      (node (ref "R11") (pin "2") (pinfunction "2_2") (pintype "passive"))
    )
    (net (code "78") (name "Net-(OP10-Pad3)") (class "Default")
      (node (ref "OP10") (pin "3") (pinfunction "3_3") (pintype "bidirectional"))
      (node (ref "R12") (pin "2") (pinfunction "2_2") (pintype "passive"))
    )
    (net (code "79") (name "Net-(OP11-Pad3)") (class "Default")
      (node (ref "OP11") (pin "3") (pinfunction "3_3") (pintype "bidirectional"))
      (node (ref "R13") (pin "2") (pinfunction "2_2") (pintype "passive"))
    )
    (net (code "80") (name "Net-(OP12-Pad3)") (class "Default")
      (node (ref "OP12") (pin "3") (pinfunction "3_3") (pintype "bidirectional"))
      (node (ref "R14") (pin "2") (pinfunction "2_2") (pintype "passive"))
    )
    (net (code "81") (name "Net-(OP13-Pad3)") (class "Default")
      (node (ref "OP13") (pin "3") (pinfunction "3_3") (pintype "bidirectional"))
      (node (ref "R15") (pin "2") (pinfunction "2_2") (pintype "passive"))
    )
    (net (code "82") (name "Net-(OP14-Pad3)") (class "Default")
      (node (ref "OP14") (pin "3") (pinfunction "3_3") (pintype "bidirectional"))
      (node (ref "R16") (pin "2") (pinfunction "2_2") (pintype "passive"))
    )
    (net (code "83") (name "Net-(R17-Pad2)") (class "Default")
      (node (ref "R17") (pin "2") (pinfunction "2_2") (pintype "passive"))
      (node (ref "R18") (pin "2") (pinfunction "2_2") (pintype "passive"))
      (node (ref "T1") (pin "B") (pinfunction "B_B") (pintype "passive"))
    )
    (net (code "84") (name "Net-(R23-Pad1)") (class "Default")
      (node (ref "R23") (pin "1") (pinfunction "1_1") (pintype "passive"))
      (node (ref "RX433") (pin "2") (pinfunction "2_2") (pintype "passive"))
      (node (ref "RX433") (pin "3") (pinfunction "3_3") (pintype "passive"))
    )
    (net (code "85") (name "Net-(TELEINFOA-KL)") (class "Default")
      (node (ref "R1") (pin "1") (pinfunction "1_1") (pintype "passive"))
      (node (ref "TELEINFO") (pin "1") (pinfunction "KL_1") (pintype "passive"))
    )
    (net (code "86") (name "Net-(WS2812-VDD)") (class "Default")
      (node (ref "C2") (pin "1") (pinfunction "1_1") (pintype "passive"))
      (node (ref "RGB") (pin "2") (pinfunction "2_2") (pintype "passive"))
      (node (ref "WS2812") (pin "2") (pinfunction "VDD_2") (pintype "power_in"))
    )
    (net (code "87") (name "PHASE") (class "Default")
      (node (ref "230V") (pin "1") (pinfunction "KL_1") (pintype "passive"))
      (node (ref "OP1") (pin "6") (pinfunction "6_6") (pintype "bidirectional"))
      (node (ref "OP10") (pin "6") (pinfunction "6_6") (pintype "bidirectional"))
      (node (ref "OP11") (pin "6") (pinfunction "6_6") (pintype "bidirectional"))
      (node (ref "OP12") (pin "6") (pinfunction "6_6") (pintype "bidirectional"))
      (node (ref "OP13") (pin "6") (pinfunction "6_6") (pintype "bidirectional"))
      (node (ref "OP14") (pin "6") (pinfunction "6_6") (pintype "bidirectional"))
      (node (ref "OP2") (pin "6") (pinfunction "6_6") (pintype "bidirectional"))
      (node (ref "OP3") (pin "6") (pinfunction "6_6") (pintype "bidirectional"))
      (node (ref "OP4") (pin "6") (pinfunction "6_6") (pintype "bidirectional"))
      (node (ref "OP5") (pin "6") (pinfunction "6_6") (pintype "bidirectional"))
      (node (ref "OP6") (pin "6") (pinfunction "6_6") (pintype "bidirectional"))
      (node (ref "OP7") (pin "6") (pinfunction "6_6") (pintype "bidirectional"))
      (node (ref "OP8") (pin "6") (pinfunction "6_6") (pintype "bidirectional"))
      (node (ref "OP9") (pin "6") (pinfunction "6_6") (pintype "bidirectional"))
    )
    (net (code "88") (name "SCL") (class "Default")
      (node (ref "I2C_OLED") (pin "3") (pinfunction "3_3") (pintype "passive"))
      (node (ref "IC1") (pin "12") (pinfunction "SCL_12") (pintype "input"))
      (node (ref "J2") (pin "1") (pinfunction "1_1") (pintype "bidirectional"))
      (node (ref "JP1") (pin "2") (pinfunction "2_2") (pintype "passive"))
      (node (ref "JP4") (pin "2") (pinfunction "2_2") (pintype "passive"))
      (node (ref "PARTICLE") (pin "14") (pinfunction "D1_14") (pintype "bidirectional"))
      (node (ref "R20") (pin "1") (pinfunction "1_1") (pintype "passive"))
    )
    (net (code "89") (name "SDA") (class "Default")
      (node (ref "I2C_OLED") (pin "4") (pinfunction "4_4") (pintype "passive"))
      (node (ref "IC1") (pin "13") (pinfunction "SDA_13") (pintype "bidirectional"))
      (node (ref "J2") (pin "2") (pinfunction "2_2") (pintype "bidirectional"))
      (node (ref "JP1") (pin "1") (pinfunction "1_1") (pintype "passive"))
      (node (ref "JP4") (pin "1") (pinfunction "1_1") (pintype "passive"))
      (node (ref "PARTICLE") (pin "13") (pinfunction "D0_13") (pintype "bidirectional"))
      (node (ref "R19") (pin "1") (pinfunction "1_1") (pintype "passive"))
    )
    (net (code "90") (name "unconnected-(IC1-INTA-Pad20)") (class "Default")
      (node (ref "IC1") (pin "20") (pinfunction "INTA_20") (pintype "output"))
    )
    (net (code "91") (name "unconnected-(IC1-INTB-Pad19)") (class "Default")
      (node (ref "IC1") (pin "19") (pinfunction "INTB_19") (pintype "output"))
    )
    (net (code "92") (name "unconnected-(U$2-FFS-PadFSS)") (class "Default")
      (node (ref "U$2") (pin "FSS") (pinfunction "FFS_FSS") (pintype "bidirectional"))
    )
    (net (code "93") (name "unconnected-(U$2-PadNRES)") (class "Default")
      (node (ref "U$2") (pin "NRES") (pinfunction "NRES_NRES") (pintype "input"))
    )
    (net (code "94") (name "unconnected-(U$3-PadDIO2)") (class "Default")
      (node (ref "U$3") (pin "DIO2") (pinfunction "DIO2_DIO2") (pintype "open_collector"))
    )
    (net (code "95") (name "unconnected-(WS2812-DOUT-Pad4)") (class "Default")
      (node (ref "WS2812") (pin "4") (pinfunction "DOUT_4") (pintype "output"))
    )
  )
)
